# Relay_Driver.net
KiCad netlist of a schematic drawn in Altium Designer
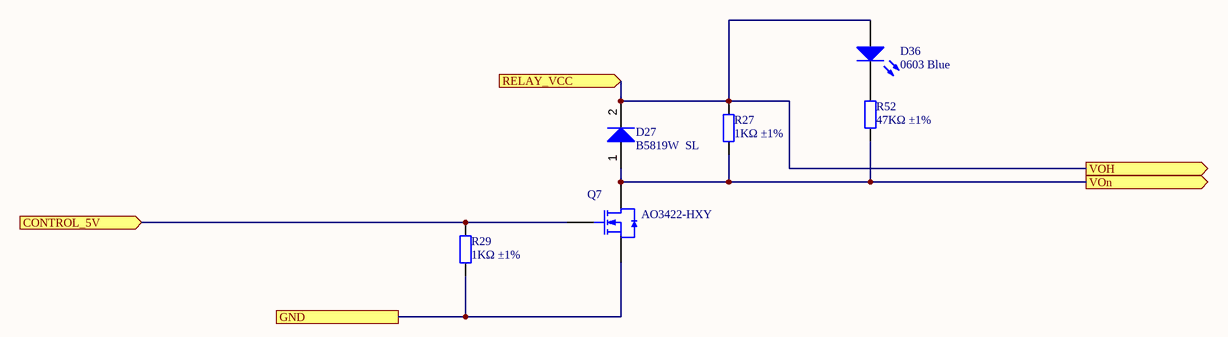
[diagram p0: Relay_Driver.SchDoc]

(export (version "E")
  (design (tool "Eeschema 10.0.6"))
  (components
    (comp (ref "D27")
      (value "B5819W  SL")
      (footprint "SOD-123")
      (description "Schottky Diode")
      (libsource (lib "Diode") (part "SOD-123 B5819W  SL"))
    )
    (comp (ref "D36")
      (value "0603 Blue")
      (footprint "0603_LED_S1")
      (description "LED")
      (libsource (lib "LED") (part "0603 LED Blue"))
    )
    (comp (ref "Q7")
      (value "AO3422-HXY")
      (footprint "SOT-23-3L")
      (description "60V 4.5A 8W 75mΩ@10V,5A 2.5V@250uA N Channel 695pF@15V SOT-23-3L MOSFETs ROHS")
      (libsource (lib "MOS") (part "AO3400A N道沟 X0YV1T SOT-23"))
    )
    (comp (ref "R27")
      (value "1KΩ ±1%")
      (footprint "0603_R")
      (description "Chip resistor")
      (fields (field (name "MANUFACTURER") "Uniroyal Elec") (field (name "PARTNUMBER") "0603WAF1001T5E"))
      (libsource (lib "RES") (part "0603 1K (1001) 1%"))
    )
    (comp (ref "R29")
      (value "1KΩ ±1%")
      (footprint "0603_R")
      (description "Chip resistor")
      (fields (field (name "MANUFACTURER") "Uniroyal Elec") (field (name "PARTNUMBER") "0603WAF1001T5E"))
      (libsource (lib "RES") (part "0603 1K (1001) 1%"))
    )
    (comp (ref "R52")
      (value "47KΩ ±1%")
      (footprint "0603_R")
      (description "Chip resistor")
      (fields (field (name "MANUFACTURER") "Uniroyal Elec") (field (name "PARTNUMBER") "0603WAF4702T5E"))
      (libsource (lib "RES") (part "0603 47K (4702) 1%"))
    )
  )
  (nets
    (net (code "1") (name "/CONTROL_5V") (class "Default")
      (node (ref "Q7") (pin "1") (pinfunction "G_1") (pintype "passive"))
      (node (ref "R29") (pin "2") (pinfunction "2_2") (pintype "passive"))
    )
    (net (code "2") (name "/GND") (class "Default")
      (node (ref "Q7") (pin "2") (pinfunction "S_2") (pintype "passive"))
      (node (ref "R29") (pin "1") (pinfunction "1_1") (pintype "passive"))
    )
    (net (code "3") (name "/RELAY_VCC") (class "Default")
      (node (ref "D27") (pin "2") (pinfunction "K_2") (pintype "passive"))
      (node (ref "D36") (pin "A") (pinfunction "A_A") (pintype "passive"))
      (node (ref "R27") (pin "2") (pinfunction "2_2") (pintype "passive"))
    )
    (net (code "4") (name "/VOn") (class "Default")
      (node (ref "D27") (pin "1") (pinfunction "A_1") (pintype "passive"))
      (node (ref "Q7") (pin "3") (pinfunction "D_3") (pintype "passive"))
      (node (ref "R27") (pin "1") (pinfunction "1_1") (pintype "passive"))
      (node (ref "R52") (pin "1") (pinfunction "1_1") (pintype "passive"))
    )
    (net (code "5") (name "Net-(D36-PadK)") (class "Default")
      (node (ref "D36") (pin "K") (pinfunction "K_K") (pintype "passive"))
      (node (ref "R52") (pin "2") (pinfunction "2_2") (pintype "passive"))
    )
  )
)
